# ESP8266Power.net
KiCad netlist of a schematic drawn in EAGLE
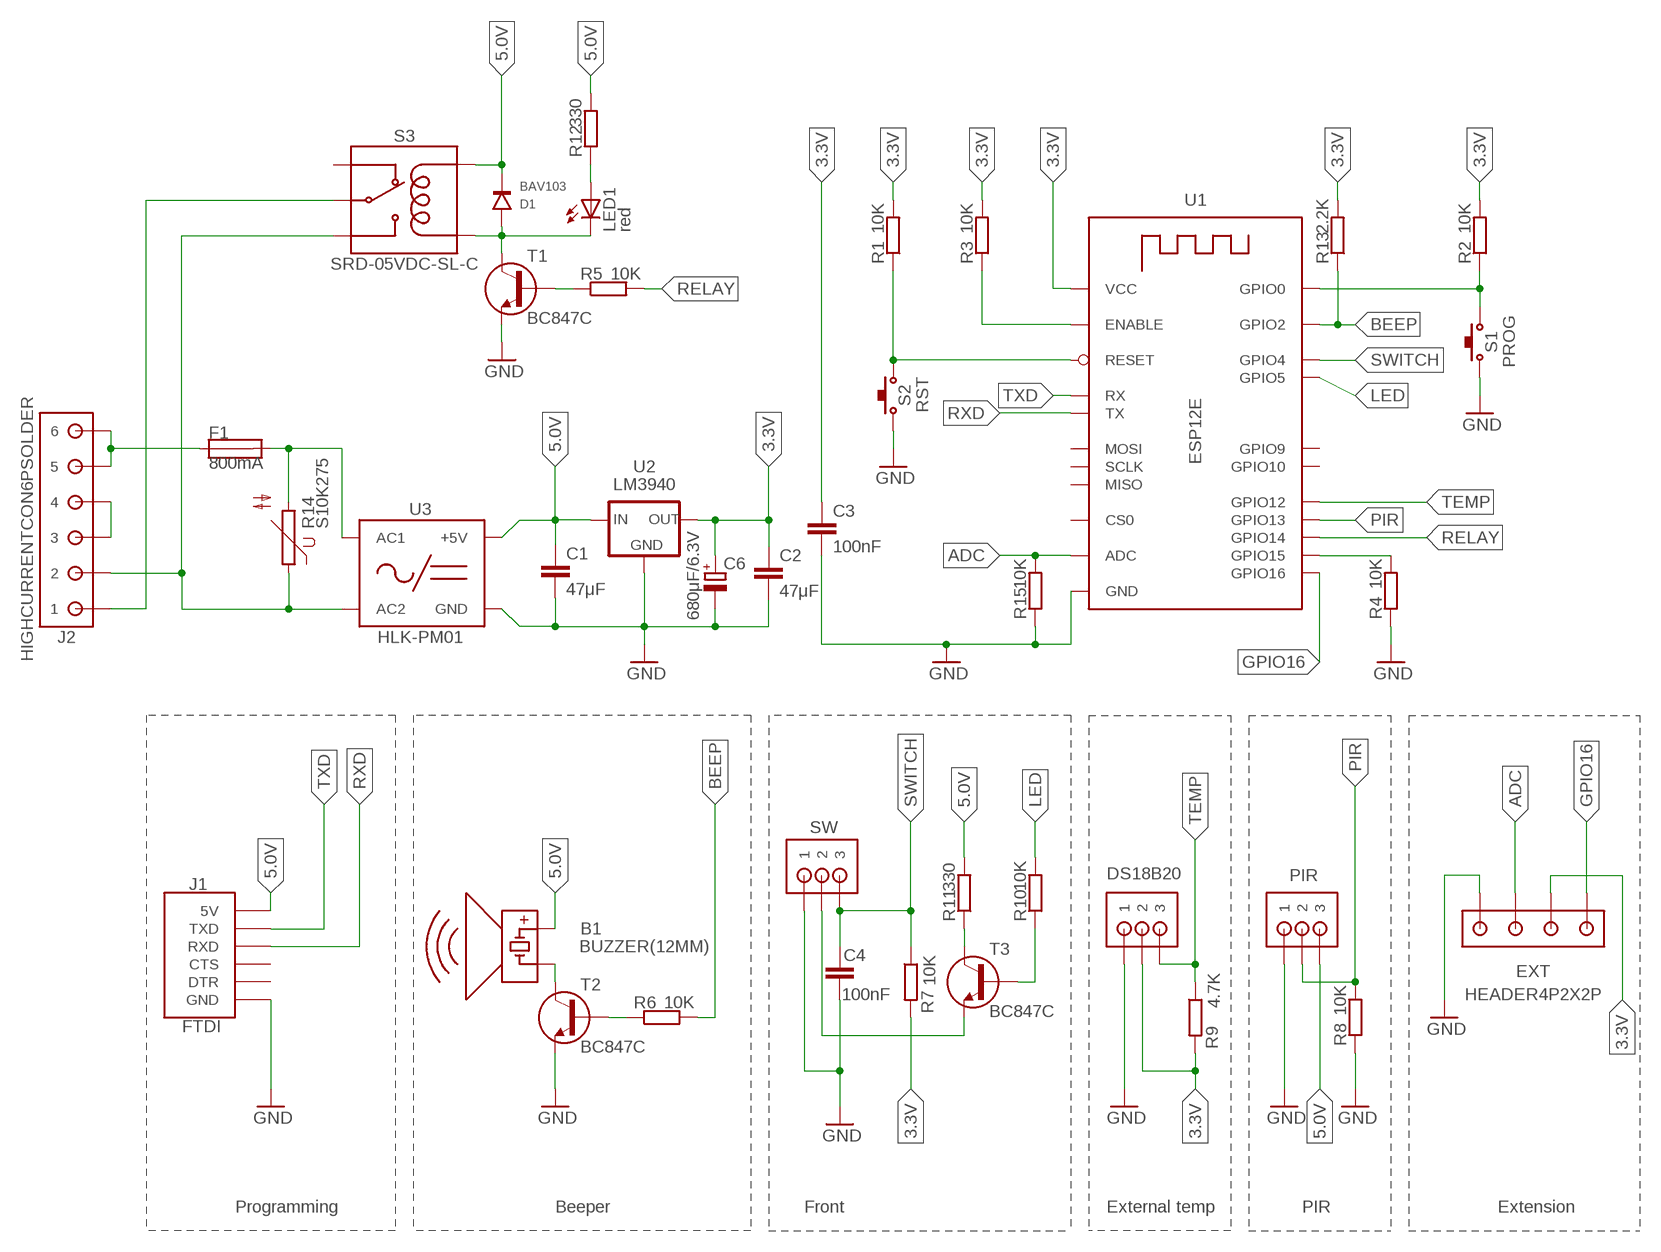
[diagram p0: schematic, sheet 1]

(export (version "E")
  (design (tool "Eeschema 10.0.6"))
  (components
    (comp (ref "B1")
      (value "BUZZER(12MM)")
      (footprint "eagle-import:BUZZER(12MM)")
      (libsource (lib "eagle-import") (part "BUZZER(12MM)"))
    )
    (comp (ref "C1")
      (value "47μF")
      (footprint "eagle-import:C1206")
      (libsource (lib "eagle-import") (part "C-EUC1206"))
    )
    (comp (ref "C2")
      (value "47μF")
      (footprint "eagle-import:C1206")
      (libsource (lib "eagle-import") (part "C-EUC1206"))
    )
    (comp (ref "C3")
      (value "100nF")
      (footprint "eagle-import:C1206")
      (libsource (lib "eagle-import") (part "C-EUC1206"))
    )
    (comp (ref "C4")
      (value "100nF")
      (footprint "eagle-import:C1206")
      (libsource (lib "eagle-import") (part "C-EUC1206"))
    )
    (comp (ref "C6")
      (value "680μF/6.3V")
      (footprint "eagle-import:E3,5-8")
      (libsource (lib "eagle-import") (part "CPOL-EUE3.5-8"))
    )
    (comp (ref "D1")
      (value "BAV103")
      (footprint "eagle-import:SOD80_DO213AA_MINIMELF")
      (libsource (lib "eagle-import") (part "BAV100-101-102-103"))
    )
    (comp (ref "DS18B20")
      (value "XH3P")
      (footprint "eagle-import:XH3P")
      (libsource (lib "eagle-import") (part "XH3P"))
    )
    (comp (ref "EXT")
      (value "HEADER4P2X2P")
      (footprint "eagle-import:HEADER2X2P")
      (libsource (lib "eagle-import") (part "HEADER4P2X2P"))
    )
    (comp (ref "F1")
      (value "800mA")
      (footprint "eagle-import:FUSE_508")
      (libsource (lib "eagle-import") (part "FUSE"))
    )
    (comp (ref "J1")
      (value "FTDI")
      (footprint "eagle-import:FTDI")
      (libsource (lib "eagle-import") (part "FTDI"))
    )
    (comp (ref "J2")
      (value "HIGHCURRENTCON6PSOLDER")
      (footprint "eagle-import:HIGHCURRENTCON6P_SOLDER")
      (libsource (lib "eagle-import") (part "HIGHCURRENTCON6PSOLDER"))
    )
    (comp (ref "LED1")
      (value "red")
      (footprint "eagle-import:CHIPLED_1206")
      (libsource (lib "eagle-import") (part "LEDCHIPLED_1206"))
    )
    (comp (ref "PIR")
      (value "XH3P")
      (footprint "eagle-import:XH3P")
      (libsource (lib "eagle-import") (part "XH3P"))
    )
    (comp (ref "R1")
      (value "10K")
      (footprint "eagle-import:R1206")
      (libsource (lib "eagle-import") (part "R-EU_R1206"))
    )
    (comp (ref "R2")
      (value "10K")
      (footprint "eagle-import:R1206")
      (libsource (lib "eagle-import") (part "R-EU_R1206"))
    )
    (comp (ref "R3")
      (value "10K")
      (footprint "eagle-import:R1206")
      (libsource (lib "eagle-import") (part "R-EU_R1206"))
    )
    (comp (ref "R4")
      (value "10K")
      (footprint "eagle-import:R1206")
      (libsource (lib "eagle-import") (part "R-EU_R1206"))
    )
    (comp (ref "R5")
      (value "10K")
      (footprint "eagle-import:R1206")
      (libsource (lib "eagle-import") (part "R-EU_R1206"))
    )
    (comp (ref "R6")
      (value "10K")
      (footprint "eagle-import:R1206")
      (libsource (lib "eagle-import") (part "R-EU_R1206"))
    )
    (comp (ref "R7")
      (value "10K")
      (footprint "eagle-import:R1206")
      (libsource (lib "eagle-import") (part "resistor_R-EU_R1206"))
    )
    (comp (ref "R8")
      (value "10K")
      (footprint "eagle-import:R1206")
      (libsource (lib "eagle-import") (part "R-EU_R1206"))
    )
    (comp (ref "R9")
      (value "4.7K")
      (footprint "eagle-import:R1206")
      (libsource (lib "eagle-import") (part "resistor_R-EU_R1206"))
    )
    (comp (ref "R10")
      (value "10K")
      (footprint "eagle-import:R1206")
      (libsource (lib "eagle-import") (part "R-EU_R1206"))
    )
    (comp (ref "R11")
      (value "330")
      (footprint "eagle-import:R1206")
      (libsource (lib "eagle-import") (part "R-EU_R1206"))
    )
    (comp (ref "R12")
      (value "330")
      (footprint "eagle-import:R1206")
      (libsource (lib "eagle-import") (part "R-EU_R1206"))
    )
    (comp (ref "R13")
      (value "2.2K")
      (footprint "eagle-import:R1206")
      (libsource (lib "eagle-import") (part "R-EU_R1206"))
    )
    (comp (ref "R14")
      (value "S10K275")
      (footprint "eagle-import:S10K275")
      (libsource (lib "eagle-import") (part "S10K275"))
    )
    (comp (ref "R15")
      (value "10K")
      (footprint "eagle-import:R1206")
      (libsource (lib "eagle-import") (part "R-EU_R1206"))
    )
    (comp (ref "S1")
      (value "PROG")
      (footprint "eagle-import:SMDPUSHBTN_TYPE1")
      (libsource (lib "eagle-import") (part "PUSHBTN"))
    )
    (comp (ref "S2")
      (value "RST")
      (footprint "eagle-import:SMDPUSHBTN_TYPE1")
      (libsource (lib "eagle-import") (part "PUSHBTN"))
    )
    (comp (ref "S3")
      (value "SRD-05VDC-SL-C")
      (footprint "eagle-import:SRD-05VDC-SL-C")
      (libsource (lib "eagle-import") (part "SRD-05VDC-SL-CPTH"))
    )
    (comp (ref "SW")
      (value "XH3P")
      (footprint "eagle-import:XH3P")
      (libsource (lib "eagle-import") (part "XH3P"))
    )
    (comp (ref "T1")
      (value "BC847C")
      (footprint "eagle-import:SOT23")
      (libsource (lib "eagle-import") (part "BC847"))
    )
    (comp (ref "T2")
      (value "BC847C")
      (footprint "eagle-import:SOT23")
      (libsource (lib "eagle-import") (part "BC847"))
    )
    (comp (ref "T3")
      (value "BC847C")
      (footprint "eagle-import:SOT23")
      (libsource (lib "eagle-import") (part "BC847"))
    )
    (comp (ref "U1")
      (value "ESP12E")
      (footprint "eagle-import:ESP8266(ESP12E)")
      (libsource (lib "eagle-import") (part "ESP8266(ESP12E)SMD"))
    )
    (comp (ref "U2")
      (value "LM3940")
      (footprint "eagle-import:SOT223")
      (libsource (lib "eagle-import") (part "LM3940"))
    )
    (comp (ref "U3")
      (value "HLK-PM01")
      (footprint "eagle-import:HLK-PM01")
      (libsource (lib "eagle-import") (part "HLK-PM01"))
    )
  )
  (nets
    (net (code "1") (name "3.3V") (class "Default")
      (node (ref "C2") (pin "1") (pinfunction "1_1") (pintype "passive"))
      (node (ref "C3") (pin "1") (pinfunction "1_1") (pintype "passive"))
      (node (ref "C6") (pin "+") (pinfunction "+_+") (pintype "passive"))
      (node (ref "DS18B20") (pin "2") (pinfunction "2_2") (pintype "bidirectional"))
      (node (ref "EXT") (pin "2") (pinfunction "2_2") (pintype "bidirectional"))
      (node (ref "R1") (pin "2") (pinfunction "2_2") (pintype "passive"))
      (node (ref "R13") (pin "2") (pinfunction "2_2") (pintype "passive"))
      (node (ref "R2") (pin "2") (pinfunction "2_2") (pintype "passive"))
      (node (ref "R3") (pin "2") (pinfunction "2_2") (pintype "passive"))
      (node (ref "R7") (pin "2") (pinfunction "2_2") (pintype "passive"))
      (node (ref "R9") (pin "2") (pinfunction "2_2") (pintype "passive"))
      (node (ref "U1") (pin "VCC") (pinfunction "VCC_VCC") (pintype "power_in"))
      (node (ref "U2") (pin "3") (pinfunction "OUT_3") (pintype "power_in"))
    )
    (net (code "2") (name "5.0V") (class "Default")
      (node (ref "B1") (pin "+") (pinfunction "+_+") (pintype "input"))
      (node (ref "C1") (pin "1") (pinfunction "1_1") (pintype "passive"))
      (node (ref "D1") (pin "C") (pinfunction "C_C") (pintype "passive"))
      (node (ref "J1") (pin "5V") (pinfunction "5V_5V") (pintype "bidirectional"))
      (node (ref "PIR") (pin "3") (pinfunction "3_3") (pintype "bidirectional"))
      (node (ref "R11") (pin "2") (pinfunction "2_2") (pintype "passive"))
      (node (ref "R12") (pin "2") (pinfunction "2_2") (pintype "passive"))
      (node (ref "S3") (pin "COIL1") (pinfunction "COIL1_COIL1") (pintype "passive"))
      (node (ref "U2") (pin "1") (pinfunction "IN_1") (pintype "input"))
      (node (ref "U3") (pin "VO+") (pinfunction "+5V_VO+") (pintype "power_in"))
    )
    (net (code "3") (name "ADC") (class "Default")
      (node (ref "EXT") (pin "3") (pinfunction "3_3") (pintype "bidirectional"))
      (node (ref "R15") (pin "2") (pinfunction "2_2") (pintype "passive"))
      (node (ref "U1") (pin "ADC") (pinfunction "ADC_ADC") (pintype "input"))
    )
    (net (code "4") (name "BEEP") (class "Default")
      (node (ref "R13") (pin "1") (pinfunction "1_1") (pintype "passive"))
      (node (ref "R6") (pin "2") (pinfunction "2_2") (pintype "passive"))
      (node (ref "U1") (pin "GPIO2") (pinfunction "GPIO2_GPIO2") (pintype "bidirectional"))
    )
    (net (code "5") (name "GND") (class "Default")
      (node (ref "C1") (pin "2") (pinfunction "2_2") (pintype "passive"))
      (node (ref "C2") (pin "2") (pinfunction "2_2") (pintype "passive"))
      (node (ref "C3") (pin "2") (pinfunction "2_2") (pintype "passive"))
      (node (ref "C4") (pin "2") (pinfunction "2_2") (pintype "passive"))
      (node (ref "C6") (pin "-") (pinfunction "-_-") (pintype "passive"))
      (node (ref "DS18B20") (pin "1") (pinfunction "1_1") (pintype "bidirectional"))
      (node (ref "EXT") (pin "4") (pinfunction "4_4") (pintype "bidirectional"))
      (node (ref "J1") (pin "GND") (pinfunction "GND_GND") (pintype "bidirectional"))
      (node (ref "PIR") (pin "1") (pinfunction "1_1") (pintype "bidirectional"))
      (node (ref "R15") (pin "1") (pinfunction "1_1") (pintype "passive"))
      (node (ref "R4") (pin "1") (pinfunction "1_1") (pintype "passive"))
      (node (ref "R8") (pin "1") (pinfunction "1_1") (pintype "passive"))
      (node (ref "S1") (pin "2") (pinfunction "2_2") (pintype "passive"))
      (node (ref "S2") (pin "2") (pinfunction "2_2") (pintype "passive"))
      (node (ref "SW") (pin "1") (pinfunction "1_1") (pintype "bidirectional"))
      (node (ref "T1") (pin "2") (pinfunction "E_2") (pintype "passive"))
      (node (ref "T2") (pin "2") (pinfunction "E_2") (pintype "passive"))
      (node (ref "U1") (pin "GND") (pinfunction "GND_GND") (pintype "passive"))
      (node (ref "U2") (pin "2") (pinfunction "GND_2") (pintype "input"))
      (node (ref "U2") (pin "4") (pinfunction "GND_4") (pintype "input"))
      (node (ref "U3") (pin "VO-") (pinfunction "GND_VO-") (pintype "power_in"))
    )
    (net (code "6") (name "GPIO16") (class "Default")
      (node (ref "EXT") (pin "1") (pinfunction "1_1") (pintype "bidirectional"))
      (node (ref "U1") (pin "GPIO16") (pinfunction "GPIO16_GPIO16") (pintype "bidirectional"))
    )
    (net (code "7") (name "LED") (class "Default")
      (node (ref "R10") (pin "2") (pinfunction "2_2") (pintype "passive"))
      (node (ref "U1") (pin "GPIO5") (pinfunction "GPIO5_GPIO5") (pintype "bidirectional"))
    )
    (net (code "8") (name "Net-(F1-Pad1)") (class "Default")
      (node (ref "F1") (pin "1") (pinfunction "1_1") (pintype "passive"))
      (node (ref "J2") (pin "5") (pinfunction "5_5") (pintype "bidirectional"))
      (node (ref "J2") (pin "6") (pinfunction "6_6") (pintype "bidirectional"))
    )
    (net (code "9") (name "Net-(F1-Pad2)") (class "Default")
      (node (ref "F1") (pin "2") (pinfunction "2_2") (pintype "passive"))
      (node (ref "R14") (pin "2") (pinfunction "2_2") (pintype "passive"))
      (node (ref "U3") (pin "AC1") (pinfunction "AC1_AC1") (pintype "input"))
    )
    (net (code "10") (name "Net-(J2-Pad1)") (class "Default")
      (node (ref "J2") (pin "1") (pinfunction "1_1") (pintype "bidirectional"))
      (node (ref "S3") (pin "SW-COMMON") (pinfunction "SW-COMMON_SW-COMMON") (pintype "passive"))
    )
    (net (code "11") (name "Net-(J2-Pad2)") (class "Default")
      (node (ref "J2") (pin "2") (pinfunction "2_2") (pintype "bidirectional"))
      (node (ref "R14") (pin "1") (pinfunction "1_1") (pintype "passive"))
      (node (ref "S3") (pin "SW-NORMAL_OPEN") (pinfunction "SW-NORMAL_OPEN_SW-NORMAL_OPEN") (pintype "passive"))
      (node (ref "U3") (pin "AC2") (pinfunction "AC2_AC2") (pintype "input"))
    )
    (net (code "12") (name "Net-(J2-Pad3)") (class "Default")
      (node (ref "J2") (pin "3") (pinfunction "3_3") (pintype "bidirectional"))
      (node (ref "J2") (pin "4") (pinfunction "4_4") (pintype "bidirectional"))
    )
    (net (code "13") (name "Net-(LED1-PadA)") (class "Default")
      (node (ref "LED1") (pin "A") (pinfunction "A_A") (pintype "passive"))
      (node (ref "R12") (pin "1") (pinfunction "1_1") (pintype "passive"))
    )
    (net (code "14") (name "Net-(R1-Pad1)") (class "Default")
      (node (ref "R1") (pin "1") (pinfunction "1_1") (pintype "passive"))
      (node (ref "S2") (pin "1") (pinfunction "1_1") (pintype "passive"))
      (node (ref "U1") (pin "RESET") (pinfunction "RESET_RESET") (pintype "input"))
    )
    (net (code "15") (name "Net-(R2-Pad1)") (class "Default")
      (node (ref "R2") (pin "1") (pinfunction "1_1") (pintype "passive"))
      (node (ref "S1") (pin "1") (pinfunction "1_1") (pintype "passive"))
      (node (ref "U1") (pin "GPIO0") (pinfunction "GPIO0_GPIO0") (pintype "bidirectional"))
    )
    (net (code "16") (name "Net-(R4-Pad2)") (class "Default")
      (node (ref "R4") (pin "2") (pinfunction "2_2") (pintype "passive"))
      (node (ref "U1") (pin "GPIO15") (pinfunction "GPIO15_GPIO15") (pintype "bidirectional"))
    )
    (net (code "17") (name "Net-(T1-B)") (class "Default")
      (node (ref "R5") (pin "1") (pinfunction "1_1") (pintype "passive"))
      (node (ref "T1") (pin "1") (pinfunction "B_1") (pintype "passive"))
    )
    (net (code "18") (name "Net-(T1-C)") (class "Default")
      (node (ref "D1") (pin "A") (pinfunction "A_A") (pintype "passive"))
      (node (ref "LED1") (pin "C") (pinfunction "C_C") (pintype "passive"))
      (node (ref "S3") (pin "COIL0") (pinfunction "COIL0_COIL0") (pintype "passive"))
      (node (ref "T1") (pin "3") (pinfunction "C_3") (pintype "passive"))
    )
    (net (code "19") (name "Net-(T2-B)") (class "Default")
      (node (ref "R6") (pin "1") (pinfunction "1_1") (pintype "passive"))
      (node (ref "T2") (pin "1") (pinfunction "B_1") (pintype "passive"))
    )
    (net (code "20") (name "Net-(T2-C)") (class "Default")
      (node (ref "B1") (pin "-") (pinfunction "-_-") (pintype "input"))
      (node (ref "T2") (pin "3") (pinfunction "C_3") (pintype "passive"))
    )
    (net (code "21") (name "Net-(T3-B)") (class "Default")
      (node (ref "R10") (pin "1") (pinfunction "1_1") (pintype "passive"))
      (node (ref "T3") (pin "1") (pinfunction "B_1") (pintype "passive"))
    )
    (net (code "22") (name "Net-(T3-C)") (class "Default")
      (node (ref "R11") (pin "1") (pinfunction "1_1") (pintype "passive"))
      (node (ref "T3") (pin "3") (pinfunction "C_3") (pintype "passive"))
    )
    (net (code "23") (name "Net-(T3-E)") (class "Default")
      (node (ref "SW") (pin "2") (pinfunction "2_2") (pintype "bidirectional"))
      (node (ref "T3") (pin "2") (pinfunction "E_2") (pintype "passive"))
    )
    (net (code "24") (name "Net-(U1-ENABLE)") (class "Default")
      (node (ref "R3") (pin "1") (pinfunction "1_1") (pintype "passive"))
      (node (ref "U1") (pin "CH_PD") (pinfunction "ENABLE_CH_PD") (pintype "input"))
    )
    (net (code "25") (name "PIR") (class "Default")
      (node (ref "PIR") (pin "2") (pinfunction "2_2") (pintype "bidirectional"))
      (node (ref "R8") (pin "2") (pinfunction "2_2") (pintype "passive"))
      (node (ref "U1") (pin "GPIO13") (pinfunction "GPIO13_GPIO13") (pintype "bidirectional"))
    )
    (net (code "26") (name "RELAY") (class "Default")
      (node (ref "R5") (pin "2") (pinfunction "2_2") (pintype "passive"))
      (node (ref "U1") (pin "GPIO14") (pinfunction "GPIO14_GPIO14") (pintype "bidirectional"))
    )
    (net (code "27") (name "RXD") (class "Default")
      (node (ref "J1") (pin "RXD") (pinfunction "RXD_RXD") (pintype "bidirectional"))
      (node (ref "U1") (pin "TXD0") (pinfunction "TX_TXD0") (pintype "output"))
    )
    (net (code "28") (name "SWITCH") (class "Default")
      (node (ref "C4") (pin "1") (pinfunction "1_1") (pintype "passive"))
      (node (ref "R7") (pin "1") (pinfunction "1_1") (pintype "passive"))
      (node (ref "SW") (pin "3") (pinfunction "3_3") (pintype "bidirectional"))
      (node (ref "U1") (pin "GPIO4") (pinfunction "GPIO4_GPIO4") (pintype "bidirectional"))
    )
    (net (code "29") (name "TEMP") (class "Default")
      (node (ref "DS18B20") (pin "3") (pinfunction "3_3") (pintype "bidirectional"))
      (node (ref "R9") (pin "1") (pinfunction "1_1") (pintype "passive"))
      (node (ref "U1") (pin "GPIO12") (pinfunction "GPIO12_GPIO12") (pintype "bidirectional"))
    )
    (net (code "30") (name "TXD") (class "Default")
      (node (ref "J1") (pin "TXD") (pinfunction "TXD_TXD") (pintype "bidirectional"))
      (node (ref "U1") (pin "RXD0") (pinfunction "RX_RXD0") (pintype "input"))
    )
    (net (code "31") (name "unconnected-(J1-PadCTS)") (class "Default")
      (node (ref "J1") (pin "CTS") (pinfunction "CTS_CTS") (pintype "bidirectional"))
    )
    (net (code "32") (name "unconnected-(J1-PadDTR)") (class "Default")
      (node (ref "J1") (pin "DTR") (pinfunction "DTR_DTR") (pintype "bidirectional"))
    )
    (net (code "33") (name "unconnected-(S3-PadSW-NORMAL_CLOSED)") (class "Default")
      (node (ref "S3") (pin "SW-NORMAL_CLOSED") (pinfunction "SW-NORMAL_CLOSED_SW-NORMAL_CLOSED") (pintype "passive"))
    )
    (net (code "34") (name "unconnected-(U1-PadCS0)") (class "Default")
      (node (ref "U1") (pin "CS0") (pinfunction "CS0_CS0") (pintype "bidirectional"))
    )
    (net (code "35") (name "unconnected-(U1-PadGPIO9)") (class "Default")
      (node (ref "U1") (pin "GPIO9") (pinfunction "GPIO9_GPIO9") (pintype "bidirectional"))
    )
    (net (code "36") (name "unconnected-(U1-PadGPIO10)") (class "Default")
      (node (ref "U1") (pin "GPIO10") (pinfunction "GPIO10_GPIO10") (pintype "bidirectional"))
    )
    (net (code "37") (name "unconnected-(U1-PadMISO)") (class "Default")
      (node (ref "U1") (pin "MISO") (pinfunction "MISO_MISO") (pintype "bidirectional"))
    )
    (net (code "38") (name "unconnected-(U1-PadMOSI)") (class "Default")
      (node (ref "U1") (pin "MOSI") (pinfunction "MOSI_MOSI") (pintype "bidirectional"))
    )
    (net (code "39") (name "unconnected-(U1-PadSCLK)") (class "Default")
      (node (ref "U1") (pin "SCLK") (pinfunction "SCLK_SCLK") (pintype "bidirectional"))
    )
  )
)
